# AMP_PROTECTION.net
KiCad netlist of a schematic drawn in Altium Designer
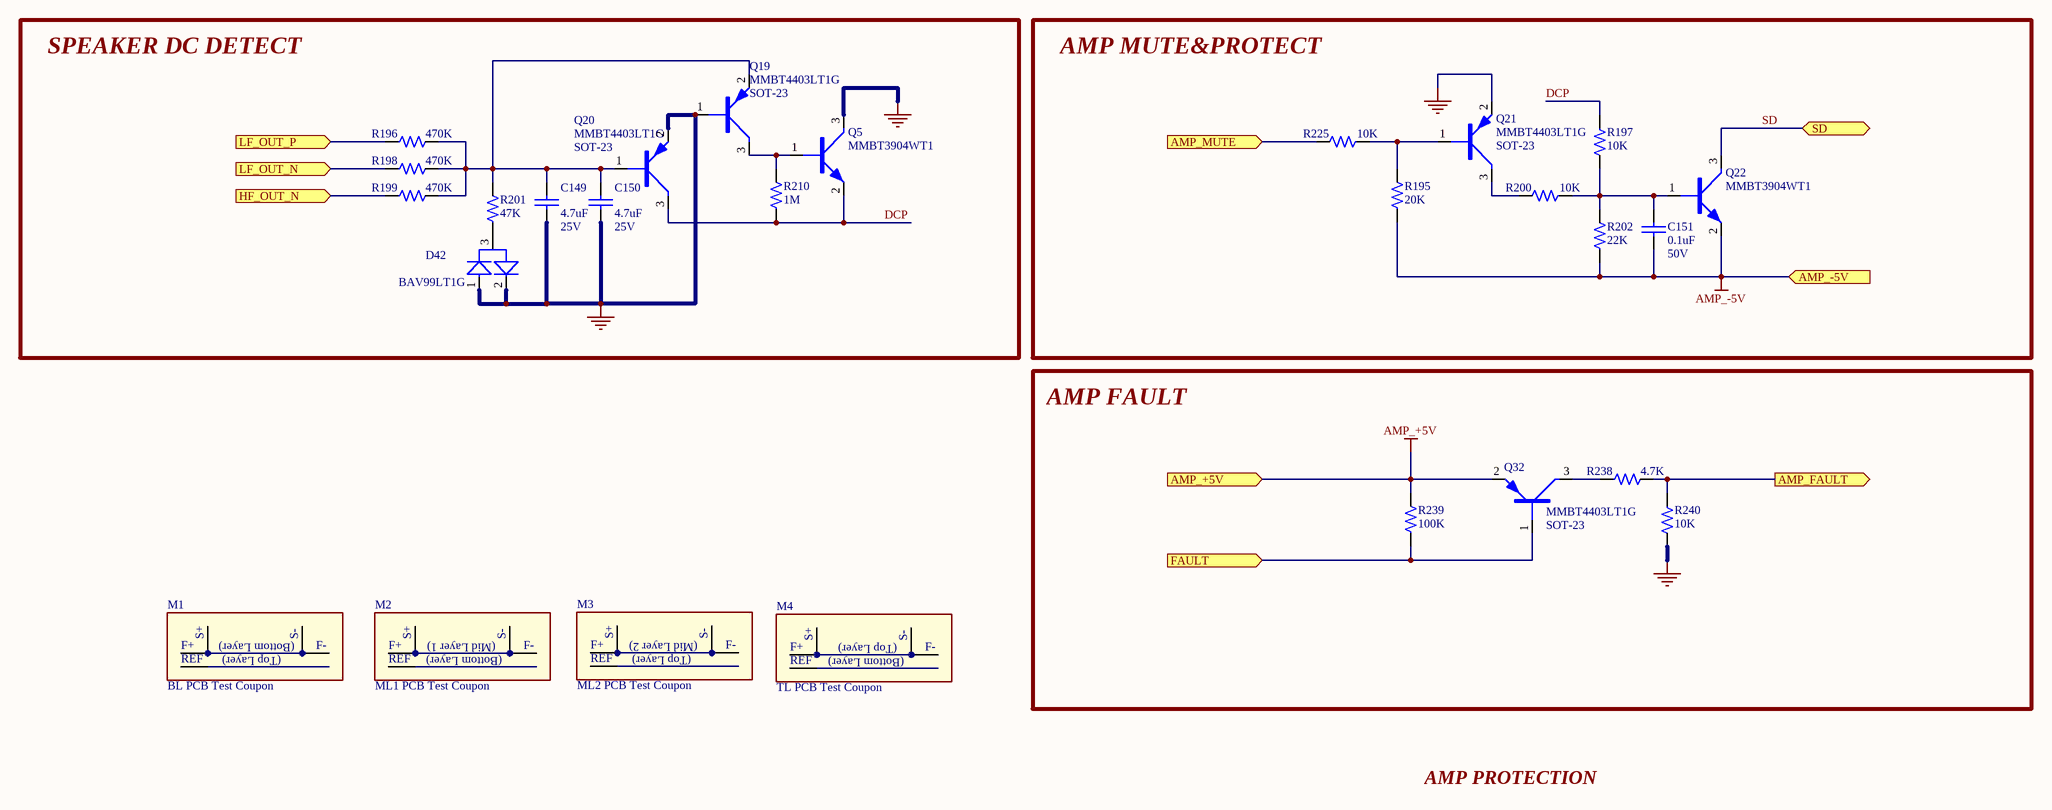
[diagram p0: AMP PROTECTION.SchDoc]

(export (version "E")
  (design (tool "Eeschema 10.0.6"))
  (components
    (comp (ref "C149")
      (value "4.7uF")
      (footprint "CAPC0603-RW")
      (description "CAP X7R 4.7UF 25V +-10% 0603 WALSIN L")
      (fields
        (field (name "MFG") "WALSIN")
        (field (name "TOLERANCE") "10%")
        (field (name "VOLTAGE") "25V")
        (field (name "CREATE_NAME") "Nathan")
      )
      (libsource (lib "P-Capacitors") (part "CAP0603 4.7uF 25V 10%_X7R_WALSIN"))
    )
    (comp (ref "C150")
      (value "4.7uF")
      (footprint "CAPC0603-RW")
      (description "CAP X7R 4.7UF 25V +-10% 0603 WALSIN L")
      (fields
        (field (name "MFG") "WALSIN")
        (field (name "TOLERANCE") "10%")
        (field (name "VOLTAGE") "25V")
        (field (name "CREATE_NAME") "Nathan")
      )
      (libsource (lib "P-Capacitors") (part "CAP0603 4.7uF 25V 10%_X7R_WALSIN"))
    )
    (comp (ref "C151")
      (value "0.1uF")
      (footprint "CAPC0603-RW")
      (description "GP CHIP CAP 0.1uF 50V 10% 0603 TYPE X7R")
      (fields
        (field (name "TOLERANCE") "10%")
        (field (name "VOLTAGE") "50V")
        (field (name "Comment") "PXL456470-1040")
      )
      (libsource (lib "Non-Suggested-Parts") (part "CAP0603 0.1uF 50V 10% - PXL456470-1040"))
    )
    (comp (ref "D42")
      (value "RCD100099-0010")
      (footprint "SOT23-132-RW")
      (description "SWITC 70V 215MA BAV99LT1G ON SE G")
      (fields
        (field (name "MFG") "ON SEMI")
        (field (name "VOLTAGE") "100V")
        (field (name "MFG PART") "BAV99LT1G")
      )
      (libsource (lib "R-Semiconductors") (part "BAV99LT1G"))
    )
    (comp (ref "M1")
      (value "Test Coupon")
      (footprint "M_BL_TL_PCB_Test_Coupon")
      (description "Bottom-Layer PCB Test Coupon (REF plane on Top Layer)")
      (fields (field (name "TEXT FIELD1") "BL PCB Test Coupon"))
      (libsource (lib "Yetta_Lib") (part "M_BL_TL_PCB_Test_Coupon"))
    )
    (comp (ref "M2")
      (value "Test Coupon")
      (footprint "M_ML1_BL_PCB_Test_Coupon")
      (description "Mid-Layer1 PCB Test Coupon (REF  plane on Bottom Layer)")
      (fields (field (name "TEXT FIELD1") "ML1 PCB Test Coupon"))
      (libsource (lib "Yetta_Lib") (part "M_ML1_BL_PCB_Test_Coupon"))
    )
    (comp (ref "M3")
      (value "Test Coupon")
      (footprint "M_ML2_TL_PCB_Test_Coupon")
      (description "Mid-Layer2 PCB Test Coupon (REF  plane on Top Layer)")
      (fields (field (name "TEXT FIELD1") "ML2 PCB Test Coupon"))
      (libsource (lib "Yetta_Lib") (part "M_ML2_TL_PCB_Test_Coupon"))
    )
    (comp (ref "M4")
      (value "Test Coupon")
      (footprint "M_TL_BL_PCB_Test_Coupon")
      (description "Top-Layer PCB Test Coupon (REF  plane on Bottom Layer)")
      (fields (field (name "TEXT FIELD1") "TL PCB Test Coupon"))
      (libsource (lib "Yetta_Lib") (part "M_TL_BL_PCB_Test_Coupon"))
    )
    (comp (ref "Q5")
      (value "T581003992440")
      (footprint "SOT323(SC-70)-R")
      (description "NPN 40V MMBT3904WT1 SC70 ( ON K")
      (fields
        (field (name "MFG") "ON")
        (field (name "MFG PART") "MMBT3904WT1")
        (field (name "CREATE_NAME") "Nathan")
      )
      (libsource (lib "R-Semiconductors") (part "MMBT3904WT1"))
    )
    (comp (ref "Q19")
      (value "T582003100440")
      (footprint "SOT23-132-RW")
      (description "PNP -40V MMBT4403LT1G SOT23 ON K")
      (fields
        (field (name "MFG") "ON")
        (field (name "VOLTAGE") "40V")
        (field (name "MFG PART") "MMBT4403LT1G")
        (field (name "PACKAGE") "SOT-23")
        (field (name "CREATE NAME") "Nathan")
      )
      (libsource (lib "R-Semiconductors") (part "MMBT4403LT1G"))
    )
    (comp (ref "Q20")
      (value "T582003100440")
      (footprint "SOT23-132-RW")
      (description "PNP -40V MMBT4403LT1G SOT23 ON K")
      (fields
        (field (name "MFG") "ON")
        (field (name "VOLTAGE") "40V")
        (field (name "MFG PART") "MMBT4403LT1G")
        (field (name "PACKAGE") "SOT-23")
        (field (name "CREATE NAME") "Nathan")
      )
      (libsource (lib "R-Semiconductors") (part "MMBT4403LT1G"))
    )
    (comp (ref "Q21")
      (value "T582003100440")
      (footprint "SOT23-132-RW")
      (description "PNP -40V MMBT4403LT1G SOT23 ON K")
      (fields
        (field (name "MFG") "ON")
        (field (name "VOLTAGE") "40V")
        (field (name "MFG PART") "MMBT4403LT1G")
        (field (name "PACKAGE") "SOT-23")
        (field (name "CREATE NAME") "Nathan")
      )
      (libsource (lib "R-Semiconductors") (part "MMBT4403LT1G"))
    )
    (comp (ref "Q22")
      (value "T581003992440")
      (footprint "SOT323(SC-70)-R")
      (description "NPN 40V MMBT3904WT1 SC70 ( ON K")
      (fields
        (field (name "MFG") "ON")
        (field (name "MFG PART") "MMBT3904WT1")
        (field (name "CREATE_NAME") "Nathan")
      )
      (libsource (lib "R-Semiconductors") (part "MMBT3904WT1"))
    )
    (comp (ref "Q32")
      (value "T582003100440")
      (footprint "SOT23-132-RW")
      (description "PNP -40V MMBT4403LT1G SOT23 ON K")
      (fields
        (field (name "MFG") "ON")
        (field (name "VOLTAGE") "40V")
        (field (name "MFG PART") "MMBT4403LT1G")
        (field (name "PACKAGE") "SOT-23")
        (field (name "CREATE NAME") "Nathan")
      )
      (libsource (lib "R-Semiconductors") (part "MMBT4403LT1G"))
    )
    (comp (ref "R195")
      (value "20K")
      (footprint "0603-RW")
      (description "GP CHIP RES. 20K OHM 1/10W 1% 0603")
      (fields (field (name "POWER") "1/10W") (field (name "Comment") "QCF011030-2002"))
      (libsource (lib "Q-Resistors") (part "RES0603 1/10W 1% 20K OHM"))
    )
    (comp (ref "R196")
      (value "470K")
      (footprint "0603-RW")
      (description "CHIP RES. 470K OHM 1/10W 1% 0603")
      (fields (field (name "POWER") "1/10W") (field (name "Comment") "QCF011030-4703"))
      (libsource (lib "Q-Resistors") (part "RES0603 1/10W 1% 470K OHM"))
    )
    (comp (ref "R197")
      (value "10K")
      (footprint "0603-RW")
      (description "GP CHIP RES. 10K OHM 1/10W 1% 0603")
      (fields (field (name "POWER") "1/10W") (field (name "Comment") "QCF011030-1002"))
      (libsource (lib "Q-Resistors") (part "RES0603 1/10W 1% 10K OHM"))
    )
    (comp (ref "R198")
      (value "470K")
      (footprint "0603-RW")
      (description "CHIP RES. 470K OHM 1/10W 1% 0603")
      (fields (field (name "POWER") "1/10W") (field (name "Comment") "QCF011030-4703"))
      (libsource (lib "Q-Resistors") (part "RES0603 1/10W 1% 470K OHM"))
    )
    (comp (ref "R199")
      (value "470K")
      (footprint "0603-RW")
      (description "CHIP RES. 470K OHM 1/10W 1% 0603")
      (fields (field (name "POWER") "1/10W") (field (name "Comment") "QCF011030-4703"))
      (libsource (lib "Q-Resistors") (part "RES0603 1/10W 1% 470K OHM"))
    )
    (comp (ref "R200")
      (value "10K")
      (footprint "0603-RW")
      (description "GP CHIP RES. 10K OHM 1/10W 1% 0603")
      (fields (field (name "POWER") "1/10W") (field (name "Comment") "QCF011030-1002"))
      (libsource (lib "Q-Resistors") (part "RES0603 1/10W 1% 10K OHM"))
    )
    (comp (ref "R201")
      (value "47K")
      (footprint "0603-RW")
      (description "GP CHIP RES. 47K OHM 1/10W 1% 0603")
      (fields (field (name "POWER") "1/10W") (field (name "Comment") "QCF011030-4702"))
      (libsource (lib "Q-Resistors") (part "RES0603 1/10W 1% 47K OHM"))
    )
    (comp (ref "R202")
      (value "22K")
      (footprint "0603-RW")
      (description "GP CHIP RES. 22K OHM 1/10W 1% 0603")
      (fields (field (name "POWER") "1/10W") (field (name "Comment") "QCF011030-2202"))
      (libsource (lib "Q-Resistors") (part "RES0603 1/10W 1% 22K OHM"))
    )
    (comp (ref "R210")
      (value "1M")
      (footprint "0603-RW")
      (description "GP CHIP RES. 1M OHM 1/10W 1% 0603")
      (fields (field (name "POWER") "1/10W") (field (name "Comment") "QCF011030-1004"))
      (libsource (lib "Q-Resistors") (part "RES0603 1/10W 1% 1M OHM"))
    )
    (comp (ref "R225")
      (value "10K")
      (footprint "0603-RW")
      (description "GP CHIP RES. 10K OHM 1/10W 1% 0603")
      (fields (field (name "POWER") "1/10W") (field (name "Comment") "QCF011030-1002"))
      (libsource (lib "Q-Resistors") (part "RES0603 1/10W 1% 10K OHM"))
    )
    (comp (ref "R238")
      (value "4.7K")
      (footprint "0603-RW")
      (description "GP CHIP RES. 4.7K OHM 1/10W 1% 0603")
      (fields (field (name "POWER") "1/10W") (field (name "Comment") "QCF011030-4701"))
      (libsource (lib "Q-Resistors") (part "RES0603 1/10W 1% 4.7K OHM"))
    )
    (comp (ref "R239")
      (value "100K")
      (footprint "0603-RW")
      (description "GP CHIP RES. 100K OHM 1/10W 1% 0603")
      (fields (field (name "POWER") "1/10W") (field (name "Comment") "QCF011030-1003"))
      (libsource (lib "Q-Resistors") (part "RES0603 1/10W 1% 100K OHM"))
    )
    (comp (ref "R240")
      (value "10K")
      (footprint "0603-RW")
      (description "GP CHIP RES. 10K OHM 1/10W 1% 0603")
      (fields (field (name "POWER") "1/10W") (field (name "Comment") "QCF011030-1002"))
      (libsource (lib "Q-Resistors") (part "RES0603 1/10W 1% 10K OHM"))
    )
  )
  (nets
    (net (code "1") (name "/AMP_FAULT") (class "Default")
      (node (ref "R238") (pin "2") (pinfunction "2_2") (pintype "passive"))
      (node (ref "R240") (pin "1") (pinfunction "1_1") (pintype "passive"))
    )
    (net (code "2") (name "/AMP_MUTE") (class "Default")
      (node (ref "R225") (pin "2") (pinfunction "2_2") (pintype "passive"))
    )
    (net (code "3") (name "/DCP") (class "Default")
      (node (ref "Q20") (pin "3") (pinfunction "C_3") (pintype "passive"))
      (node (ref "Q5") (pin "2") (pinfunction "E_2") (pintype "passive"))
      (node (ref "R197") (pin "1") (pinfunction "1_1") (pintype "passive"))
      (node (ref "R210") (pin "1") (pinfunction "1_1") (pintype "passive"))
    )
    (net (code "4") (name "/FAULT") (class "Default")
      (node (ref "Q32") (pin "1") (pinfunction "B_1") (pintype "passive"))
      (node (ref "R239") (pin "1") (pinfunction "1_1") (pintype "passive"))
    )
    (net (code "5") (name "/HF_OUT_N") (class "Default")
      (node (ref "R199") (pin "1") (pinfunction "1_1") (pintype "passive"))
    )
    (net (code "6") (name "/LF_OUT_N") (class "Default")
      (node (ref "R198") (pin "1") (pinfunction "1_1") (pintype "passive"))
    )
    (net (code "7") (name "/LF_OUT_P") (class "Default")
      (node (ref "R196") (pin "1") (pinfunction "1_1") (pintype "passive"))
    )
    (net (code "8") (name "/SD") (class "Default")
      (node (ref "Q22") (pin "3") (pinfunction "C_3") (pintype "passive"))
    )
    (net (code "9") (name "AMP_+5V") (class "Default")
      (node (ref "Q32") (pin "2") (pinfunction "E_2") (pintype "passive"))
      (node (ref "R239") (pin "2") (pinfunction "2_2") (pintype "passive"))
    )
    (net (code "10") (name "AMP_-5V") (class "Default")
      (node (ref "C151") (pin "2") (pinfunction "2_2") (pintype "passive"))
      (node (ref "Q22") (pin "2") (pinfunction "E_2") (pintype "passive"))
      (node (ref "R195") (pin "1") (pinfunction "1_1") (pintype "passive"))
      (node (ref "R202") (pin "1") (pinfunction "1_1") (pintype "passive"))
    )
    (net (code "11") (name "GND") (class "Default")
      (node (ref "C149") (pin "2") (pinfunction "2_2") (pintype "passive"))
      (node (ref "C150") (pin "2") (pinfunction "2_2") (pintype "passive"))
      (node (ref "D42") (pin "1") (pinfunction "A_1") (pintype "passive"))
      (node (ref "D42") (pin "2") (pinfunction "A_2") (pintype "passive"))
      (node (ref "Q19") (pin "1") (pinfunction "B_1") (pintype "passive"))
      (node (ref "Q20") (pin "2") (pinfunction "E_2") (pintype "passive"))
      (node (ref "Q21") (pin "2") (pinfunction "E_2") (pintype "passive"))
      (node (ref "Q5") (pin "3") (pinfunction "C_3") (pintype "passive"))
      (node (ref "R240") (pin "2") (pinfunction "2_2") (pintype "passive"))
    )
    (net (code "12") (name "Net-(D42-K)") (class "Default")
      (node (ref "D42") (pin "3") (pinfunction "K_3") (pintype "passive"))
      (node (ref "R201") (pin "1") (pinfunction "1_1") (pintype "passive"))
    )
    (net (code "13") (name "Net-(Q19-C)") (class "Default")
      (node (ref "Q19") (pin "3") (pinfunction "C_3") (pintype "passive"))
      (node (ref "Q5") (pin "1") (pinfunction "B_1") (pintype "passive"))
      (node (ref "R210") (pin "2") (pinfunction "2_2") (pintype "passive"))
    )
    (net (code "14") (name "Net-(Q19-E)") (class "Default")
      (node (ref "C149") (pin "1") (pinfunction "1_1") (pintype "passive"))
      (node (ref "C150") (pin "1") (pinfunction "1_1") (pintype "passive"))
      (node (ref "Q19") (pin "2") (pinfunction "E_2") (pintype "passive"))
      (node (ref "Q20") (pin "1") (pinfunction "B_1") (pintype "passive"))
      (node (ref "R196") (pin "2") (pinfunction "2_2") (pintype "passive"))
      (node (ref "R198") (pin "2") (pinfunction "2_2") (pintype "passive"))
      (node (ref "R199") (pin "2") (pinfunction "2_2") (pintype "passive"))
      (node (ref "R201") (pin "2") (pinfunction "2_2") (pintype "passive"))
    )
    (net (code "15") (name "Net-(Q21-B)") (class "Default")
      (node (ref "Q21") (pin "1") (pinfunction "B_1") (pintype "passive"))
      (node (ref "R195") (pin "2") (pinfunction "2_2") (pintype "passive"))
      (node (ref "R225") (pin "1") (pinfunction "1_1") (pintype "passive"))
    )
    (net (code "16") (name "Net-(Q21-C)") (class "Default")
      (node (ref "Q21") (pin "3") (pinfunction "C_3") (pintype "passive"))
      (node (ref "R200") (pin "2") (pinfunction "2_2") (pintype "passive"))
    )
    (net (code "17") (name "Net-(Q22-B)") (class "Default")
      (node (ref "C151") (pin "1") (pinfunction "1_1") (pintype "passive"))
      (node (ref "Q22") (pin "1") (pinfunction "B_1") (pintype "passive"))
      (node (ref "R197") (pin "2") (pinfunction "2_2") (pintype "passive"))
      (node (ref "R200") (pin "1") (pinfunction "1_1") (pintype "passive"))
      (node (ref "R202") (pin "2") (pinfunction "2_2") (pintype "passive"))
    )
    (net (code "18") (name "Net-(Q32-C)") (class "Default")
      (node (ref "Q32") (pin "3") (pinfunction "C_3") (pintype "passive"))
      (node (ref "R238") (pin "1") (pinfunction "1_1") (pintype "passive"))
    )
  )
)
